# ZYNQ400-MIO.net
KiCad netlist of a schematic drawn in Altium Designer
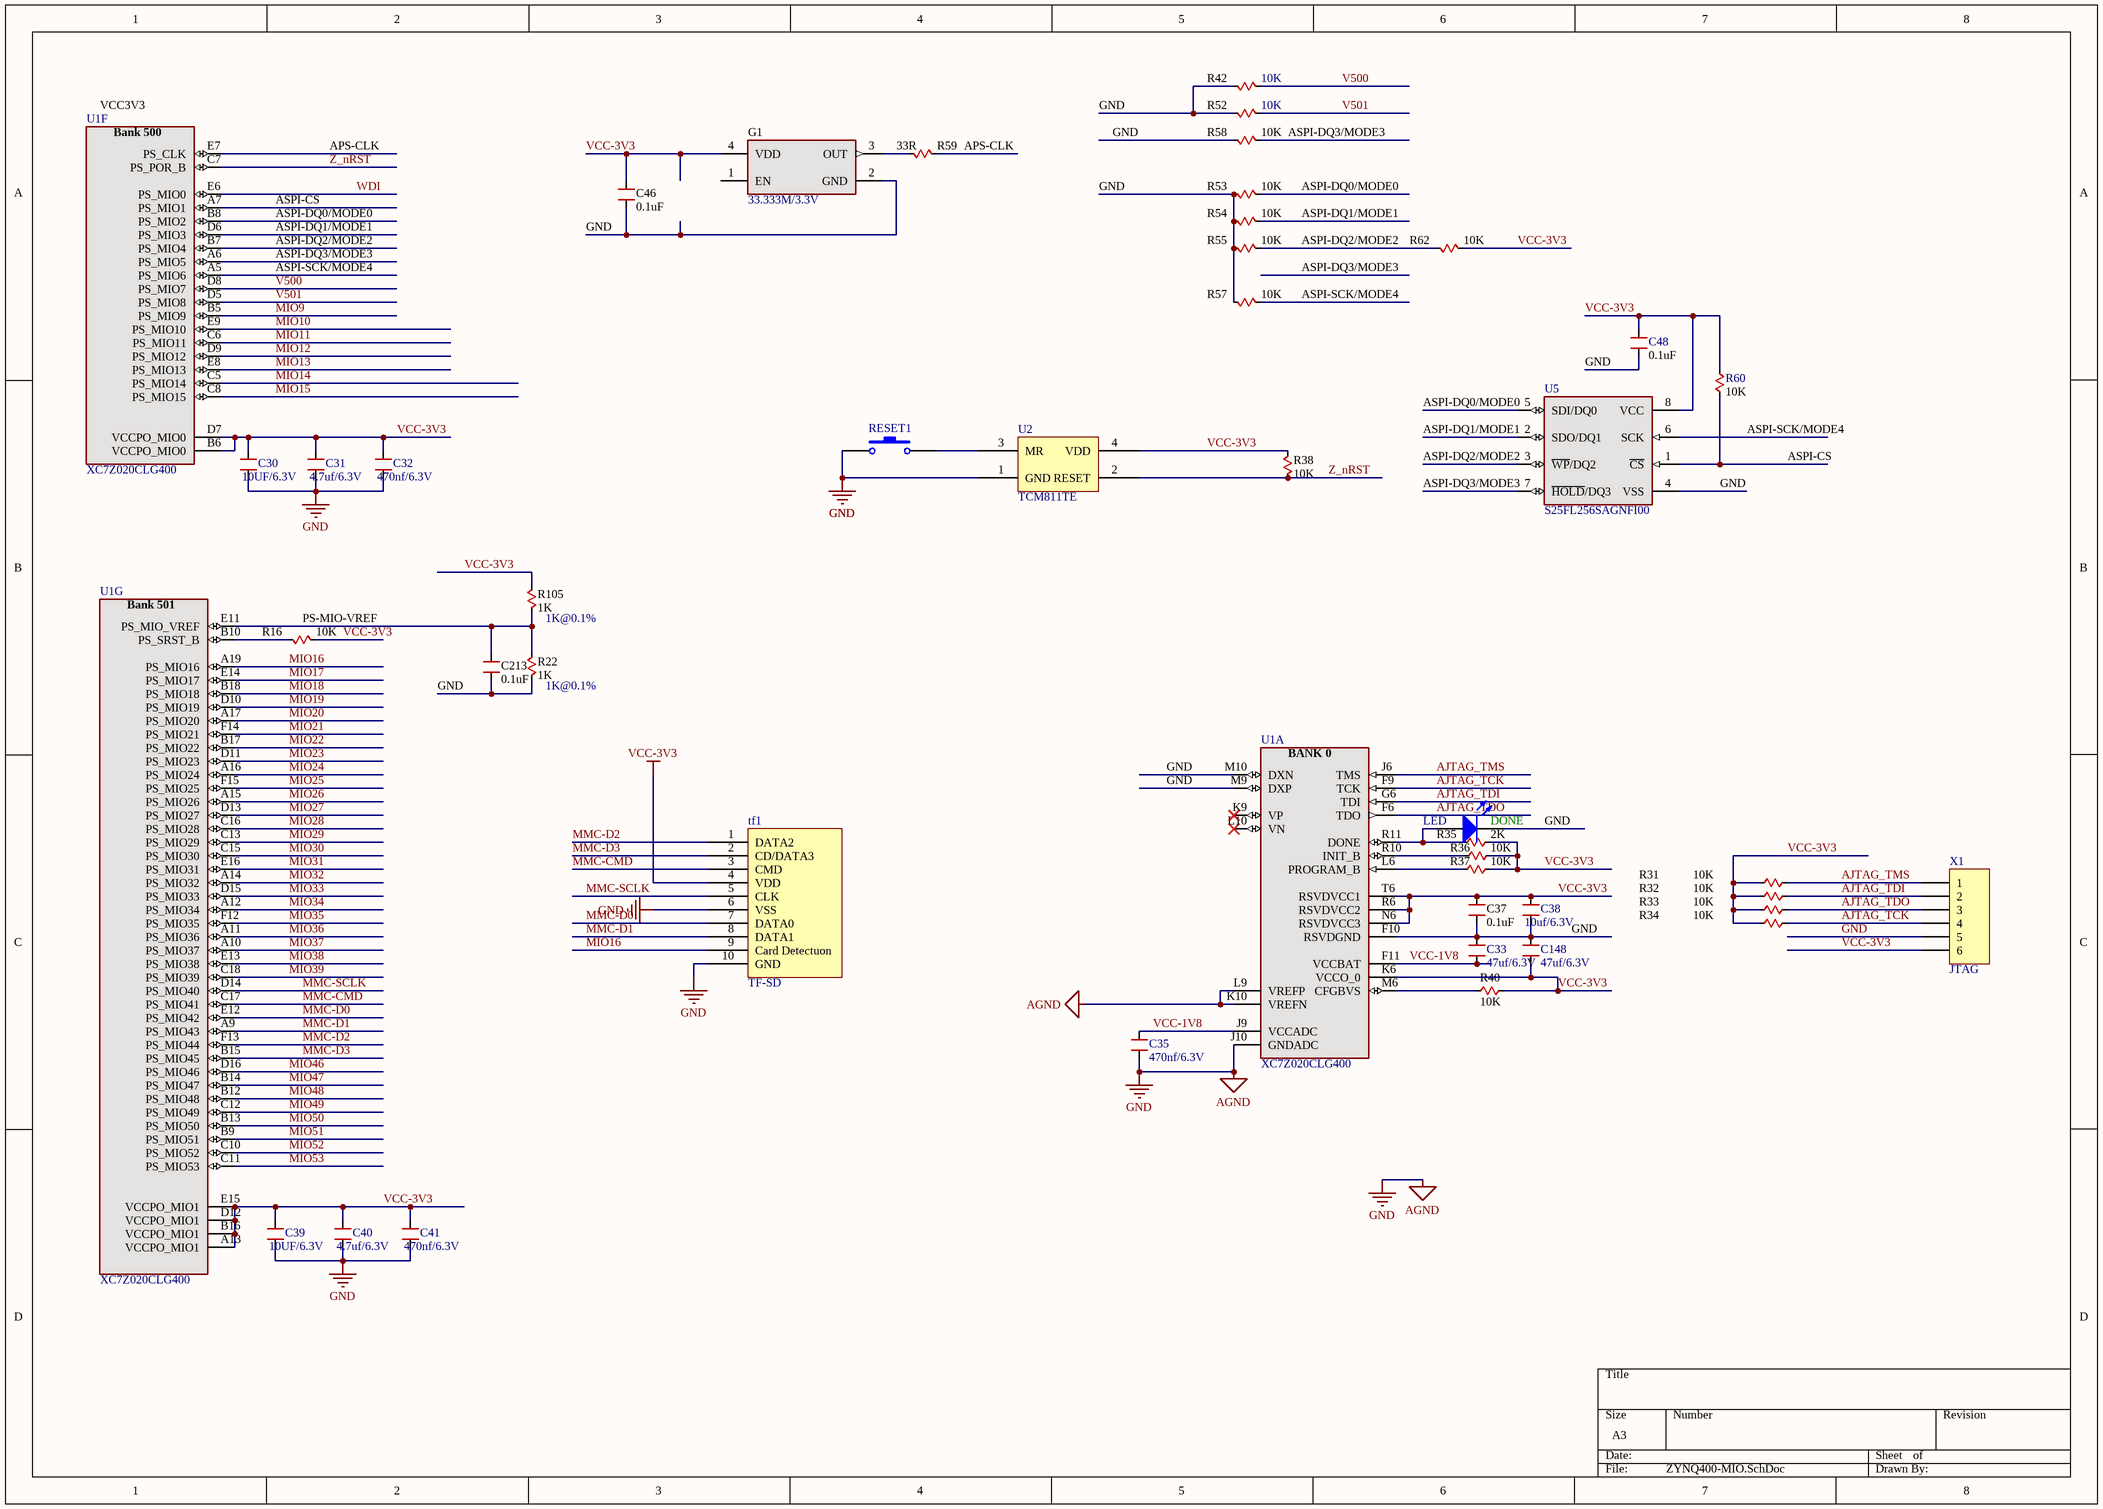
[diagram p0: ZYNQ400-MIO.SchDoc]

(export (version "E")
  (design (tool "Eeschema 10.0.6"))
  (components
    (comp (ref "C30")
      (value "10UF/6.3V")
      (footprint "0402")
      (description "Generic Capacitor")
      (libsource (lib "Digilent") (part "CAPACITOR"))
    )
    (comp (ref "C31")
      (value "4.7uf/6.3V")
      (footprint "0402")
      (description "Generic Capacitor")
      (libsource (lib "Digilent") (part "CAPACITOR"))
    )
    (comp (ref "C32")
      (value "470nf/6.3V")
      (footprint "0402")
      (description "Generic Capacitor")
      (libsource (lib "Digilent") (part "CAPACITOR"))
    )
    (comp (ref "C33")
      (value "47uf/6.3V")
      (footprint "0402")
      (description "Generic Capacitor")
      (libsource (lib "Digilent") (part "CAPACITOR"))
    )
    (comp (ref "C35")
      (value "470nf/6.3V")
      (footprint "0402")
      (description "Generic Capacitor")
      (libsource (lib "Digilent") (part "CAPACITOR"))
    )
    (comp (ref "C37")
      (value "0.1uF")
      (footprint "0402")
      (description "Generic Capacitor")
      (fields (field (name "Comment") "0.1UF"))
      (libsource (lib "Digilent") (part "CAPACITOR"))
    )
    (comp (ref "C38")
      (value "10uf/6.3V")
      (footprint "0603")
      (description "Generic Capacitor")
      (libsource (lib "Digilent") (part "CAPACITOR"))
    )
    (comp (ref "C39")
      (value "10UF/6.3V")
      (footprint "0402")
      (description "Generic Capacitor")
      (libsource (lib "Digilent") (part "CAPACITOR"))
    )
    (comp (ref "C40")
      (value "4.7uf/6.3V")
      (footprint "0402")
      (description "Generic Capacitor")
      (libsource (lib "Digilent") (part "CAPACITOR"))
    )
    (comp (ref "C41")
      (value "470nf/6.3V")
      (footprint "0402")
      (description "Generic Capacitor")
      (libsource (lib "Digilent") (part "CAPACITOR"))
    )
    (comp (ref "C46")
      (value "0.1uF")
      (footprint "0402")
      (description "Generic Capacitor")
      (fields (field (name "Comment") "0.1UF"))
      (libsource (lib "Digilent") (part "CAPACITOR"))
    )
    (comp (ref "C48")
      (value "0.1uF")
      (footprint "0402")
      (description "Generic Capacitor")
      (fields (field (name "Comment") "0.1UF"))
      (libsource (lib "Digilent") (part "CAPACITOR"))
    )
    (comp (ref "C148")
      (value "47uf/6.3V")
      (footprint "0402")
      (description "Generic Capacitor")
      (libsource (lib "Digilent") (part "CAPACITOR"))
    )
    (comp (ref "C213")
      (value "0.1uF")
      (footprint "0402")
      (description "Generic Capacitor")
      (libsource (lib "Digilent") (part "CAPACITOR"))
    )
    (comp (ref "DONE")
      (value "LED")
      (footprint "D0402")
      (description "Typical INFRARED GaAs LED")
      (fields (field (name "PUBLISHER") "Altium Limited"))
      (libsource (lib "Miscellaneous Devices") (part "LED0"))
    )
    (comp (ref "G1")
      (value "33.333M/3.3V")
      (footprint "3.2*2.5")
      (description "3.3V HCMOS Oscillator")
      (fields (field (name "MANUFACTURER") "Fox Electronics"))
      (libsource (lib "Digilent") (part "FXO-HC5"))
    )
    (comp (ref "R16")
      (value "10K")
      (footprint "0402")
      (description "Generic Resistor")
      (libsource (lib "Digilent") (part "RESISTOR"))
    )
    (comp (ref "R22")
      (value "1K@0.1%")
      (footprint "0402")
      (description "Generic Resistor")
      (fields (field (name "ALTIUM_VALUE") "1K"))
      (libsource (lib "Digilent") (part "RESISTOR"))
    )
    (comp (ref "R31")
      (value "10K")
      (footprint "0402")
      (description "Generic Resistor")
      (libsource (lib "Digilent") (part "RESISTOR"))
    )
    (comp (ref "R32")
      (value "10K")
      (footprint "0402")
      (description "Generic Resistor")
      (libsource (lib "Digilent") (part "RESISTOR"))
    )
    (comp (ref "R33")
      (value "10K")
      (footprint "0402")
      (description "Generic Resistor")
      (libsource (lib "Digilent") (part "RESISTOR"))
    )
    (comp (ref "R34")
      (value "10K")
      (footprint "0402")
      (description "Generic Resistor")
      (libsource (lib "Digilent") (part "RESISTOR"))
    )
    (comp (ref "R35")
      (value "2K")
      (footprint "0402")
      (description "Generic Resistor")
      (fields (field (name "Comment") "1K"))
      (libsource (lib "Digilent") (part "RESISTOR"))
    )
    (comp (ref "R36")
      (value "10K")
      (footprint "0402")
      (description "Generic Resistor")
      (libsource (lib "Digilent") (part "RESISTOR"))
    )
    (comp (ref "R37")
      (value "10K")
      (footprint "0402")
      (description "Generic Resistor")
      (libsource (lib "Digilent") (part "RESISTOR"))
    )
    (comp (ref "R38")
      (value "10K")
      (footprint "0402")
      (description "Generic Resistor")
      (libsource (lib "Digilent") (part "RESISTOR"))
    )
    (comp (ref "R40")
      (value "10K")
      (footprint "0402")
      (description "Generic Resistor")
      (libsource (lib "Digilent") (part "RESISTOR"))
    )
    (comp (ref "R42")
      (value "10K")
      (footprint "0402")
      (description "Generic Resistor")
      (libsource (lib "Digilent") (part "RESISTOR"))
    )
    (comp (ref "R52")
      (value "10K")
      (footprint "0402")
      (description "Generic Resistor")
      (libsource (lib "Digilent") (part "RESISTOR"))
    )
    (comp (ref "R53")
      (value "10K")
      (footprint "0402")
      (description "Generic Resistor")
      (libsource (lib "Digilent") (part "RESISTOR"))
    )
    (comp (ref "R54")
      (value "10K")
      (footprint "0402")
      (description "Generic Resistor")
      (libsource (lib "Digilent") (part "RESISTOR"))
    )
    (comp (ref "R55")
      (value "10K")
      (footprint "0402")
      (description "Generic Resistor")
      (libsource (lib "Digilent") (part "RESISTOR"))
    )
    (comp (ref "R57")
      (value "10K")
      (footprint "0402")
      (description "Generic Resistor")
      (libsource (lib "Digilent") (part "RESISTOR"))
    )
    (comp (ref "R58")
      (value "10K")
      (footprint "0402")
      (description "Generic Resistor")
      (libsource (lib "Digilent") (part "RESISTOR"))
    )
    (comp (ref "R59")
      (value "33R")
      (footprint "0402")
      (description "Generic Resistor")
      (libsource (lib "Digilent") (part "RESISTOR"))
    )
    (comp (ref "R60")
      (value "10K")
      (footprint "0402")
      (description "Generic Resistor")
      (libsource (lib "Digilent") (part "RESISTOR"))
    )
    (comp (ref "R62")
      (value "10K")
      (footprint "0402")
      (description "Generic Resistor")
      (libsource (lib "Digilent") (part "RESISTOR"))
    )
    (comp (ref "R105")
      (value "1K@0.1%")
      (footprint "0402")
      (description "Generic Resistor")
      (fields (field (name "ALTIUM_VALUE") "1K"))
      (libsource (lib "Digilent") (part "RESISTOR"))
    )
    (comp (ref "RESET1")
      (value "SW-PB")
      (footprint "micro button_2_SMD")
      (description "Switch")
      (fields (field (name "PUBLISHER") "Altium Limited"))
      (libsource (lib "M4(3333)") (part "SW-PB"))
    )
    (comp (ref "tf1") (value "TF-SD") (footprint "TF") (libsource (lib "M4(3333)") (part "TF-SD")))
    (comp (ref "U1")
      (value "XC7Z020CLG400")
      (footprint "CLG400")
      (description "Zynq 7000 FPGA 20 Die, in a CSG 484 Package")
      (fields (field (name "MANUFACTURER") "Xilinx"))
      (libsource (lib "gjws") (part "XC7Z020-CLG400"))
    )
    (comp (ref "U2") (value "TCM811TE") (footprint "TCM811TERCTR") (libsource (lib "ZYNQ") (part "TCM811TE")))
    (comp (ref "U5")
      (value "S25FL256SAGNFI00")
      (footprint "MLP8")
      (description "Serial Flash Memory, 16Mbit, Low Voltage, 50MHz SPI Bus Interface")
      (fields (field (name "MANUFACTURER") "Spansion"))
      (libsource (lib "Digilent") (part "N25Q12-F8"))
    )
    (comp (ref "X1")
      (value "JTAG")
      (footprint "1.27*6")
      (description "Header, 6-Pin")
      (fields (field (name "PUBLISHER") "Altium Limited"))
      (libsource (lib "Miscellaneous Connectors") (part "Header 6"))
    )
  )
  (nets
    (net (code "1") (name "/AJTAG_TCK") (class "Default")
      (node (ref "R34") (pin "2") (pinfunction "2_2") (pintype "passive"))
      (node (ref "U1") (pin "F9") (pinfunction "TCK_F9") (pintype "input"))
      (node (ref "X1") (pin "4") (pinfunction "4_4") (pintype "passive"))
    )
    (net (code "2") (name "/AJTAG_TDI") (class "Default")
      (node (ref "R32") (pin "2") (pinfunction "2_2") (pintype "passive"))
      (node (ref "U1") (pin "G6") (pinfunction "TDI_G6") (pintype "input"))
      (node (ref "X1") (pin "2") (pinfunction "2_2") (pintype "passive"))
    )
    (net (code "3") (name "/AJTAG_TDO") (class "Default")
      (node (ref "R33") (pin "2") (pinfunction "2_2") (pintype "passive"))
      (node (ref "U1") (pin "F6") (pinfunction "TDO_F6") (pintype "output"))
      (node (ref "X1") (pin "3") (pinfunction "3_3") (pintype "passive"))
    )
    (net (code "4") (name "/AJTAG_TMS") (class "Default")
      (node (ref "R31") (pin "2") (pinfunction "2_2") (pintype "passive"))
      (node (ref "U1") (pin "J6") (pinfunction "TMS_J6") (pintype "input"))
      (node (ref "X1") (pin "1") (pinfunction "1_1") (pintype "passive"))
    )
    (net (code "5") (name "/APS-CLK") (class "Default")
      (node (ref "R59") (pin "2") (pinfunction "2_2") (pintype "passive"))
      (node (ref "U1") (pin "E7") (pinfunction "PS_CLK_E7") (pintype "bidirectional"))
    )
    (net (code "6") (name "/ASPI-CS") (class "Default")
      (node (ref "R60") (pin "2") (pinfunction "2_2") (pintype "passive"))
      (node (ref "U1") (pin "A7") (pinfunction "PS_MIO1_A7") (pintype "bidirectional"))
      (node (ref "U5") (pin "1") (pinfunction "~{CS}_1") (pintype "input"))
    )
    (net (code "7") (name "/ASPI-DQ0{slash}MODE0") (class "Default")
      (node (ref "R53") (pin "2") (pinfunction "2_2") (pintype "passive"))
      (node (ref "U1") (pin "B8") (pinfunction "PS_MIO2_B8") (pintype "bidirectional"))
      (node (ref "U5") (pin "5") (pinfunction "SDI/DQ0_5") (pintype "bidirectional"))
    )
    (net (code "8") (name "/ASPI-DQ1{slash}MODE1") (class "Default")
      (node (ref "R54") (pin "2") (pinfunction "2_2") (pintype "passive"))
      (node (ref "U1") (pin "D6") (pinfunction "PS_MIO3_D6") (pintype "bidirectional"))
      (node (ref "U5") (pin "2") (pinfunction "SDO/DQ1_2") (pintype "bidirectional"))
    )
    (net (code "9") (name "/ASPI-DQ2{slash}MODE2") (class "Default")
      (node (ref "R55") (pin "2") (pinfunction "2_2") (pintype "passive"))
      (node (ref "R62") (pin "1") (pinfunction "1_1") (pintype "passive"))
      (node (ref "U1") (pin "B7") (pinfunction "PS_MIO4_B7") (pintype "bidirectional"))
      (node (ref "U5") (pin "3") (pinfunction "~{WP}/DQ2_3") (pintype "bidirectional"))
    )
    (net (code "10") (name "/ASPI-DQ3{slash}MODE3") (class "Default")
      (node (ref "R58") (pin "2") (pinfunction "2_2") (pintype "passive"))
      (node (ref "U1") (pin "A6") (pinfunction "PS_MIO5_A6") (pintype "bidirectional"))
      (node (ref "U5") (pin "7") (pinfunction "~{HOLD}/DQ3_7") (pintype "bidirectional"))
    )
    (net (code "11") (name "/ASPI-SCK{slash}MODE4") (class "Default")
      (node (ref "R57") (pin "2") (pinfunction "2_2") (pintype "passive"))
      (node (ref "U1") (pin "A5") (pinfunction "PS_MIO6_A5") (pintype "bidirectional"))
      (node (ref "U5") (pin "6") (pinfunction "SCK_6") (pintype "input"))
    )
    (net (code "12") (name "/MIO9") (class "Default")
      (node (ref "U1") (pin "B5") (pinfunction "PS_MIO9_B5") (pintype "bidirectional"))
    )
    (net (code "13") (name "/MIO10") (class "Default")
      (node (ref "U1") (pin "E9") (pinfunction "PS_MIO10_E9") (pintype "bidirectional"))
    )
    (net (code "14") (name "/MIO11") (class "Default")
      (node (ref "U1") (pin "C6") (pinfunction "PS_MIO11_C6") (pintype "bidirectional"))
    )
    (net (code "15") (name "/MIO12") (class "Default")
      (node (ref "U1") (pin "D9") (pinfunction "PS_MIO12_D9") (pintype "bidirectional"))
    )
    (net (code "16") (name "/MIO13") (class "Default")
      (node (ref "U1") (pin "E8") (pinfunction "PS_MIO13_E8") (pintype "bidirectional"))
    )
    (net (code "17") (name "/MIO14") (class "Default")
      (node (ref "U1") (pin "C5") (pinfunction "PS_MIO14_C5") (pintype "bidirectional"))
    )
    (net (code "18") (name "/MIO15") (class "Default")
      (node (ref "U1") (pin "C8") (pinfunction "PS_MIO15_C8") (pintype "bidirectional"))
    )
    (net (code "19") (name "/MIO16") (class "Default")
      (node (ref "U1") (pin "A19") (pinfunction "PS_MIO16_A19") (pintype "bidirectional"))
      (node (ref "tf1") (pin "9") (pinfunction "Card_Detectuon_9") (pintype "passive"))
    )
    (net (code "20") (name "/MIO17") (class "Default")
      (node (ref "U1") (pin "E14") (pinfunction "PS_MIO17_E14") (pintype "bidirectional"))
    )
    (net (code "21") (name "/MIO18") (class "Default")
      (node (ref "U1") (pin "B18") (pinfunction "PS_MIO18_B18") (pintype "bidirectional"))
    )
    (net (code "22") (name "/MIO19") (class "Default")
      (node (ref "U1") (pin "D10") (pinfunction "PS_MIO19_D10") (pintype "bidirectional"))
    )
    (net (code "23") (name "/MIO20") (class "Default")
      (node (ref "U1") (pin "A17") (pinfunction "PS_MIO20_A17") (pintype "bidirectional"))
    )
    (net (code "24") (name "/MIO21") (class "Default")
      (node (ref "U1") (pin "F14") (pinfunction "PS_MIO21_F14") (pintype "bidirectional"))
    )
    (net (code "25") (name "/MIO22") (class "Default")
      (node (ref "U1") (pin "B17") (pinfunction "PS_MIO22_B17") (pintype "bidirectional"))
    )
    (net (code "26") (name "/MIO23") (class "Default")
      (node (ref "U1") (pin "D11") (pinfunction "PS_MIO23_D11") (pintype "bidirectional"))
    )
    (net (code "27") (name "/MIO24") (class "Default")
      (node (ref "U1") (pin "A16") (pinfunction "PS_MIO24_A16") (pintype "bidirectional"))
    )
    (net (code "28") (name "/MIO25") (class "Default")
      (node (ref "U1") (pin "F15") (pinfunction "PS_MIO25_F15") (pintype "bidirectional"))
    )
    (net (code "29") (name "/MIO26") (class "Default")
      (node (ref "U1") (pin "A15") (pinfunction "PS_MIO26_A15") (pintype "bidirectional"))
    )
    (net (code "30") (name "/MIO27") (class "Default")
      (node (ref "U1") (pin "D13") (pinfunction "PS_MIO27_D13") (pintype "bidirectional"))
    )
    (net (code "31") (name "/MIO28") (class "Default")
      (node (ref "U1") (pin "C16") (pinfunction "PS_MIO28_C16") (pintype "bidirectional"))
    )
    (net (code "32") (name "/MIO29") (class "Default")
      (node (ref "U1") (pin "C13") (pinfunction "PS_MIO29_C13") (pintype "bidirectional"))
    )
    (net (code "33") (name "/MIO30") (class "Default")
      (node (ref "U1") (pin "C15") (pinfunction "PS_MIO30_C15") (pintype "bidirectional"))
    )
    (net (code "34") (name "/MIO31") (class "Default")
      (node (ref "U1") (pin "E16") (pinfunction "PS_MIO31_E16") (pintype "bidirectional"))
    )
    (net (code "35") (name "/MIO32") (class "Default")
      (node (ref "U1") (pin "A14") (pinfunction "PS_MIO32_A14") (pintype "bidirectional"))
    )
    (net (code "36") (name "/MIO33") (class "Default")
      (node (ref "U1") (pin "D15") (pinfunction "PS_MIO33_D15") (pintype "bidirectional"))
    )
    (net (code "37") (name "/MIO34") (class "Default")
      (node (ref "U1") (pin "A12") (pinfunction "PS_MIO34_A12") (pintype "bidirectional"))
    )
    (net (code "38") (name "/MIO35") (class "Default")
      (node (ref "U1") (pin "F12") (pinfunction "PS_MIO35_F12") (pintype "bidirectional"))
    )
    (net (code "39") (name "/MIO36") (class "Default")
      (node (ref "U1") (pin "A11") (pinfunction "PS_MIO36_A11") (pintype "bidirectional"))
    )
    (net (code "40") (name "/MIO37") (class "Default")
      (node (ref "U1") (pin "A10") (pinfunction "PS_MIO37_A10") (pintype "bidirectional"))
    )
    (net (code "41") (name "/MIO38") (class "Default")
      (node (ref "U1") (pin "E13") (pinfunction "PS_MIO38_E13") (pintype "bidirectional"))
    )
    (net (code "42") (name "/MIO39") (class "Default")
      (node (ref "U1") (pin "C18") (pinfunction "PS_MIO39_C18") (pintype "bidirectional"))
    )
    (net (code "43") (name "/MIO46") (class "Default")
      (node (ref "U1") (pin "D16") (pinfunction "PS_MIO46_D16") (pintype "bidirectional"))
    )
    (net (code "44") (name "/MIO47") (class "Default")
      (node (ref "U1") (pin "B14") (pinfunction "PS_MIO47_B14") (pintype "bidirectional"))
    )
    (net (code "45") (name "/MIO48") (class "Default")
      (node (ref "U1") (pin "B12") (pinfunction "PS_MIO48_B12") (pintype "bidirectional"))
    )
    (net (code "46") (name "/MIO49") (class "Default")
      (node (ref "U1") (pin "C12") (pinfunction "PS_MIO49_C12") (pintype "bidirectional"))
    )
    (net (code "47") (name "/MIO50") (class "Default")
      (node (ref "U1") (pin "B13") (pinfunction "PS_MIO50_B13") (pintype "bidirectional"))
    )
    (net (code "48") (name "/MIO51") (class "Default")
      (node (ref "U1") (pin "B9") (pinfunction "PS_MIO51_B9") (pintype "bidirectional"))
    )
    (net (code "49") (name "/MIO52") (class "Default")
      (node (ref "U1") (pin "C10") (pinfunction "PS_MIO52_C10") (pintype "bidirectional"))
    )
    (net (code "50") (name "/MIO53") (class "Default")
      (node (ref "U1") (pin "C11") (pinfunction "PS_MIO53_C11") (pintype "bidirectional"))
    )
    (net (code "51") (name "/MMC-CMD") (class "Default")
      (node (ref "U1") (pin "C17") (pinfunction "PS_MIO41_C17") (pintype "bidirectional"))
      (node (ref "tf1") (pin "3") (pinfunction "CMD_3") (pintype "passive"))
    )
    (net (code "52") (name "/MMC-D0") (class "Default")
      (node (ref "U1") (pin "E12") (pinfunction "PS_MIO42_E12") (pintype "bidirectional"))
      (node (ref "tf1") (pin "7") (pinfunction "DATA0_7") (pintype "passive"))
    )
    (net (code "53") (name "/MMC-D1") (class "Default")
      (node (ref "U1") (pin "A9") (pinfunction "PS_MIO43_A9") (pintype "bidirectional"))
      (node (ref "tf1") (pin "8") (pinfunction "DATA1_8") (pintype "passive"))
    )
    (net (code "54") (name "/MMC-D2") (class "Default")
      (node (ref "U1") (pin "F13") (pinfunction "PS_MIO44_F13") (pintype "bidirectional"))
      (node (ref "tf1") (pin "1") (pinfunction "DATA2_1") (pintype "passive"))
    )
    (net (code "55") (name "/MMC-D3") (class "Default")
      (node (ref "U1") (pin "B15") (pinfunction "PS_MIO45_B15") (pintype "bidirectional"))
      (node (ref "tf1") (pin "2") (pinfunction "CD/DATA3_2") (pintype "passive"))
    )
    (net (code "56") (name "/MMC-SCLK") (class "Default")
      (node (ref "U1") (pin "D14") (pinfunction "PS_MIO40_D14") (pintype "bidirectional"))
      (node (ref "tf1") (pin "5") (pinfunction "CLK_5") (pintype "passive"))
    )
    (net (code "57") (name "/PS-MIO-VREF") (class "Default")
      (node (ref "C213") (pin "1") (pinfunction "1_1") (pintype "passive"))
      (node (ref "R105") (pin "2") (pinfunction "2_2") (pintype "passive"))
      (node (ref "R22") (pin "1") (pinfunction "1_1") (pintype "passive"))
      (node (ref "U1") (pin "E11") (pinfunction "PS_MIO_VREF_E11") (pintype "bidirectional"))
    )
    (net (code "58") (name "/V500") (class "Default")
      (node (ref "R42") (pin "2") (pinfunction "2_2") (pintype "passive"))
      (node (ref "U1") (pin "D8") (pinfunction "PS_MIO7_D8") (pintype "bidirectional"))
    )
    (net (code "59") (name "/V501") (class "Default")
      (node (ref "R52") (pin "2") (pinfunction "2_2") (pintype "passive"))
      (node (ref "U1") (pin "D5") (pinfunction "PS_MIO8_D5") (pintype "bidirectional"))
    )
    (net (code "60") (name "/VCC-1V8") (class "Default")
      (node (ref "C33") (pin "1") (pinfunction "1_1") (pintype "passive"))
      (node (ref "C35") (pin "1") (pinfunction "1_1") (pintype "passive"))
      (node (ref "U1") (pin "F11") (pinfunction "VCCBAT_F11") (pintype "passive"))
      (node (ref "U1") (pin "J9") (pinfunction "VCCADC_J9") (pintype "passive"))
    )
    (net (code "61") (name "/WDI") (class "Default")
      (node (ref "U1") (pin "E6") (pinfunction "PS_MIO0_E6") (pintype "bidirectional"))
    )
    (net (code "62") (name "/Z_nRST") (class "Default")
      (node (ref "R38") (pin "1") (pinfunction "1_1") (pintype "passive"))
      (node (ref "U1") (pin "C7") (pinfunction "PS_POR_B_C7") (pintype "bidirectional"))
      (node (ref "U2") (pin "2") (pinfunction "RESET_2") (pintype "passive"))
    )
    (net (code "63") (name "AGND") (class "Default")
      (node (ref "C148") (pin "2") (pinfunction "2_2") (pintype "passive"))
      (node (ref "C213") (pin "2") (pinfunction "2_2") (pintype "passive"))
      (node (ref "C30") (pin "2") (pinfunction "2_2") (pintype "passive"))
      (node (ref "C31") (pin "2") (pinfunction "2_2") (pintype "passive"))
      (node (ref "C32") (pin "2") (pinfunction "2_2") (pintype "passive"))
      (node (ref "C33") (pin "2") (pinfunction "2_2") (pintype "passive"))
      (node (ref "C35") (pin "2") (pinfunction "2_2") (pintype "passive"))
      (node (ref "C37") (pin "2") (pinfunction "2_2") (pintype "passive"))
      (node (ref "C38") (pin "2") (pinfunction "2_2") (pintype "passive"))
      (node (ref "C39") (pin "2") (pinfunction "2_2") (pintype "passive"))
      (node (ref "C40") (pin "2") (pinfunction "2_2") (pintype "passive"))
      (node (ref "C41") (pin "2") (pinfunction "2_2") (pintype "passive"))
      (node (ref "C46") (pin "2") (pinfunction "2_2") (pintype "passive"))
      (node (ref "C48") (pin "2") (pinfunction "2_2") (pintype "passive"))
      (node (ref "DONE") (pin "2") (pinfunction "K_2") (pintype "passive"))
      (node (ref "G1") (pin "2") (pinfunction "GND_2") (pintype "power_in"))
      (node (ref "R22") (pin "2") (pinfunction "2_2") (pintype "passive"))
      (node (ref "R42") (pin "1") (pinfunction "1_1") (pintype "passive"))
      (node (ref "R52") (pin "1") (pinfunction "1_1") (pintype "passive"))
      (node (ref "R53") (pin "1") (pinfunction "1_1") (pintype "passive"))
      (node (ref "R54") (pin "1") (pinfunction "1_1") (pintype "passive"))
      (node (ref "R55") (pin "1") (pinfunction "1_1") (pintype "passive"))
      (node (ref "R57") (pin "1") (pinfunction "1_1") (pintype "passive"))
      (node (ref "R58") (pin "1") (pinfunction "1_1") (pintype "passive"))
      (node (ref "RESET1") (pin "1") (pinfunction "1_1") (pintype "passive"))
      (node (ref "U1") (pin "F10") (pinfunction "RSVDGND_F10") (pintype "power_in"))
      (node (ref "U1") (pin "J10") (pinfunction "GNDADC_J10") (pintype "passive"))
      (node (ref "U1") (pin "K10") (pinfunction "VREFN_K10") (pintype "passive"))
      (node (ref "U1") (pin "L9") (pinfunction "VREFP_L9") (pintype "passive"))
      (node (ref "U1") (pin "M10") (pinfunction "DXN_M10") (pintype "bidirectional"))
      (node (ref "U1") (pin "M9") (pinfunction "DXP_M9") (pintype "bidirectional"))
      (node (ref "U2") (pin "1") (pinfunction "GND_1") (pintype "passive"))
      (node (ref "U5") (pin "4") (pinfunction "VSS_4") (pintype "power_in"))
      (node (ref "X1") (pin "5") (pinfunction "5_5") (pintype "passive"))
      (node (ref "tf1") (pin "10") (pinfunction "GND_10") (pintype "passive"))
      (node (ref "tf1") (pin "6") (pinfunction "VSS_6") (pintype "passive"))
    )
    (net (code "64") (name "Net-(DONE-A)") (class "Default")
      (node (ref "DONE") (pin "1") (pinfunction "A_1") (pintype "passive"))
      (node (ref "R35") (pin "1") (pinfunction "1_1") (pintype "passive"))
      (node (ref "U1") (pin "R11") (pinfunction "DONE_R11") (pintype "bidirectional"))
    )
    (net (code "65") (name "Net-(G1-OUT)") (class "Default")
      (node (ref "G1") (pin "3") (pinfunction "OUT_3") (pintype "output"))
      (node (ref "R59") (pin "1") (pinfunction "1_1") (pintype "passive"))
    )
    (net (code "66") (name "Net-(U1A-CFGBVS)") (class "Default")
      (node (ref "R40") (pin "1") (pinfunction "1_1") (pintype "passive"))
      (node (ref "U1") (pin "M6") (pinfunction "CFGBVS_M6") (pintype "bidirectional"))
    )
    (net (code "67") (name "Net-(U1A-INIT_B)") (class "Default")
      (node (ref "R36") (pin "2") (pinfunction "2_2") (pintype "passive"))
      (node (ref "U1") (pin "R10") (pinfunction "INIT_B_R10") (pintype "bidirectional"))
    )
    (net (code "68") (name "Net-(U1A-PROGRAM_B)") (class "Default")
      (node (ref "R37") (pin "1") (pinfunction "1_1") (pintype "passive"))
      (node (ref "U1") (pin "L6") (pinfunction "PROGRAM_B_L6") (pintype "input"))
    )
    (net (code "69") (name "Net-(U1G-PS_SRST_B)") (class "Default")
      (node (ref "R16") (pin "1") (pinfunction "1_1") (pintype "passive"))
      (node (ref "U1") (pin "B10") (pinfunction "PS_SRST_B_B10") (pintype "bidirectional"))
    )
    (net (code "70") (name "Net-(U2-MR)") (class "Default")
      (node (ref "RESET1") (pin "2") (pinfunction "2_2") (pintype "passive"))
      (node (ref "U2") (pin "3") (pinfunction "MR_3") (pintype "passive"))
    )
    (net (code "71") (name "VCC-3V3") (class "Default")
      (node (ref "C148") (pin "1") (pinfunction "1_1") (pintype "passive"))
      (node (ref "C30") (pin "1") (pinfunction "1_1") (pintype "passive"))
      (node (ref "C31") (pin "1") (pinfunction "1_1") (pintype "passive"))
      (node (ref "C32") (pin "1") (pinfunction "1_1") (pintype "passive"))
      (node (ref "C37") (pin "1") (pinfunction "1_1") (pintype "passive"))
      (node (ref "C38") (pin "1") (pinfunction "1_1") (pintype "passive"))
      (node (ref "C39") (pin "1") (pinfunction "1_1") (pintype "passive"))
      (node (ref "C40") (pin "1") (pinfunction "1_1") (pintype "passive"))
      (node (ref "C41") (pin "1") (pinfunction "1_1") (pintype "passive"))
      (node (ref "C46") (pin "1") (pinfunction "1_1") (pintype "passive"))
      (node (ref "C48") (pin "1") (pinfunction "1_1") (pintype "passive"))
      (node (ref "G1") (pin "4") (pinfunction "VDD_4") (pintype "power_in"))
      (node (ref "R105") (pin "1") (pinfunction "1_1") (pintype "passive"))
      (node (ref "R16") (pin "2") (pinfunction "2_2") (pintype "passive"))
      (node (ref "R31") (pin "1") (pinfunction "1_1") (pintype "passive"))
      (node (ref "R32") (pin "1") (pinfunction "1_1") (pintype "passive"))
      (node (ref "R33") (pin "1") (pinfunction "1_1") (pintype "passive"))
      (node (ref "R34") (pin "1") (pinfunction "1_1") (pintype "passive"))
      (node (ref "R35") (pin "2") (pinfunction "2_2") (pintype "passive"))
      (node (ref "R36") (pin "1") (pinfunction "1_1") (pintype "passive"))
      (node (ref "R37") (pin "2") (pinfunction "2_2") (pintype "passive"))
      (node (ref "R38") (pin "2") (pinfunction "2_2") (pintype "passive"))
      (node (ref "R40") (pin "2") (pinfunction "2_2") (pintype "passive"))
      (node (ref "R60") (pin "1") (pinfunction "1_1") (pintype "passive"))
      (node (ref "R62") (pin "2") (pinfunction "2_2") (pintype "passive"))
      (node (ref "U1") (pin "A13") (pinfunction "VCCPO_MIO1_A13") (pintype "power_in"))
      (node (ref "U1") (pin "B16") (pinfunction "VCCPO_MIO1_B16") (pintype "power_in"))
      (node (ref "U1") (pin "B6") (pinfunction "VCCPO_MIO0_B6") (pintype "power_in"))
      (node (ref "U1") (pin "D12") (pinfunction "VCCPO_MIO1_D12") (pintype "power_in"))
      (node (ref "U1") (pin "D7") (pinfunction "VCCPO_MIO0_D7") (pintype "power_in"))
      (node (ref "U1") (pin "E15") (pinfunction "VCCPO_MIO1_E15") (pintype "power_in"))
      (node (ref "U1") (pin "K6") (pinfunction "VCCO_0_K6") (pintype "power_in"))
      (node (ref "U1") (pin "N6") (pinfunction "RSVDVCC3_N6") (pintype "power_in"))
      (node (ref "U1") (pin "R6") (pinfunction "RSVDVCC2_R6") (pintype "power_in"))
      (node (ref "U1") (pin "T6") (pinfunction "RSVDVCC1_T6") (pintype "power_in"))
      (node (ref "U2") (pin "4") (pinfunction "VDD_4") (pintype "passive"))
      (node (ref "U5") (pin "8") (pinfunction "VCC_8") (pintype "power_in"))
      (node (ref "X1") (pin "6") (pinfunction "6_6") (pintype "passive"))
      (node (ref "tf1") (pin "4") (pinfunction "VDD_4") (pintype "passive"))
    )
    (net (code "72") (name "unconnected-(G1-EN-Pad1)") (class "Default")
      (node (ref "G1") (pin "1") (pinfunction "EN_1") (pintype "passive"))
    )
    (net (code "73") (name "unconnected-(U1A-VN-PadL10)") (class "Default")
      (node (ref "U1") (pin "L10") (pinfunction "VN_L10") (pintype "bidirectional+no_connect"))
    )
    (net (code "74") (name "unconnected-(U1A-VP-PadK9)") (class "Default")
      (node (ref "U1") (pin "K9") (pinfunction "VP_K9") (pintype "bidirectional+no_connect"))
    )
  )
)
